# Edin_Usher_DRV2630_reference_design.net
KiCad netlist of a schematic drawn in EAGLE
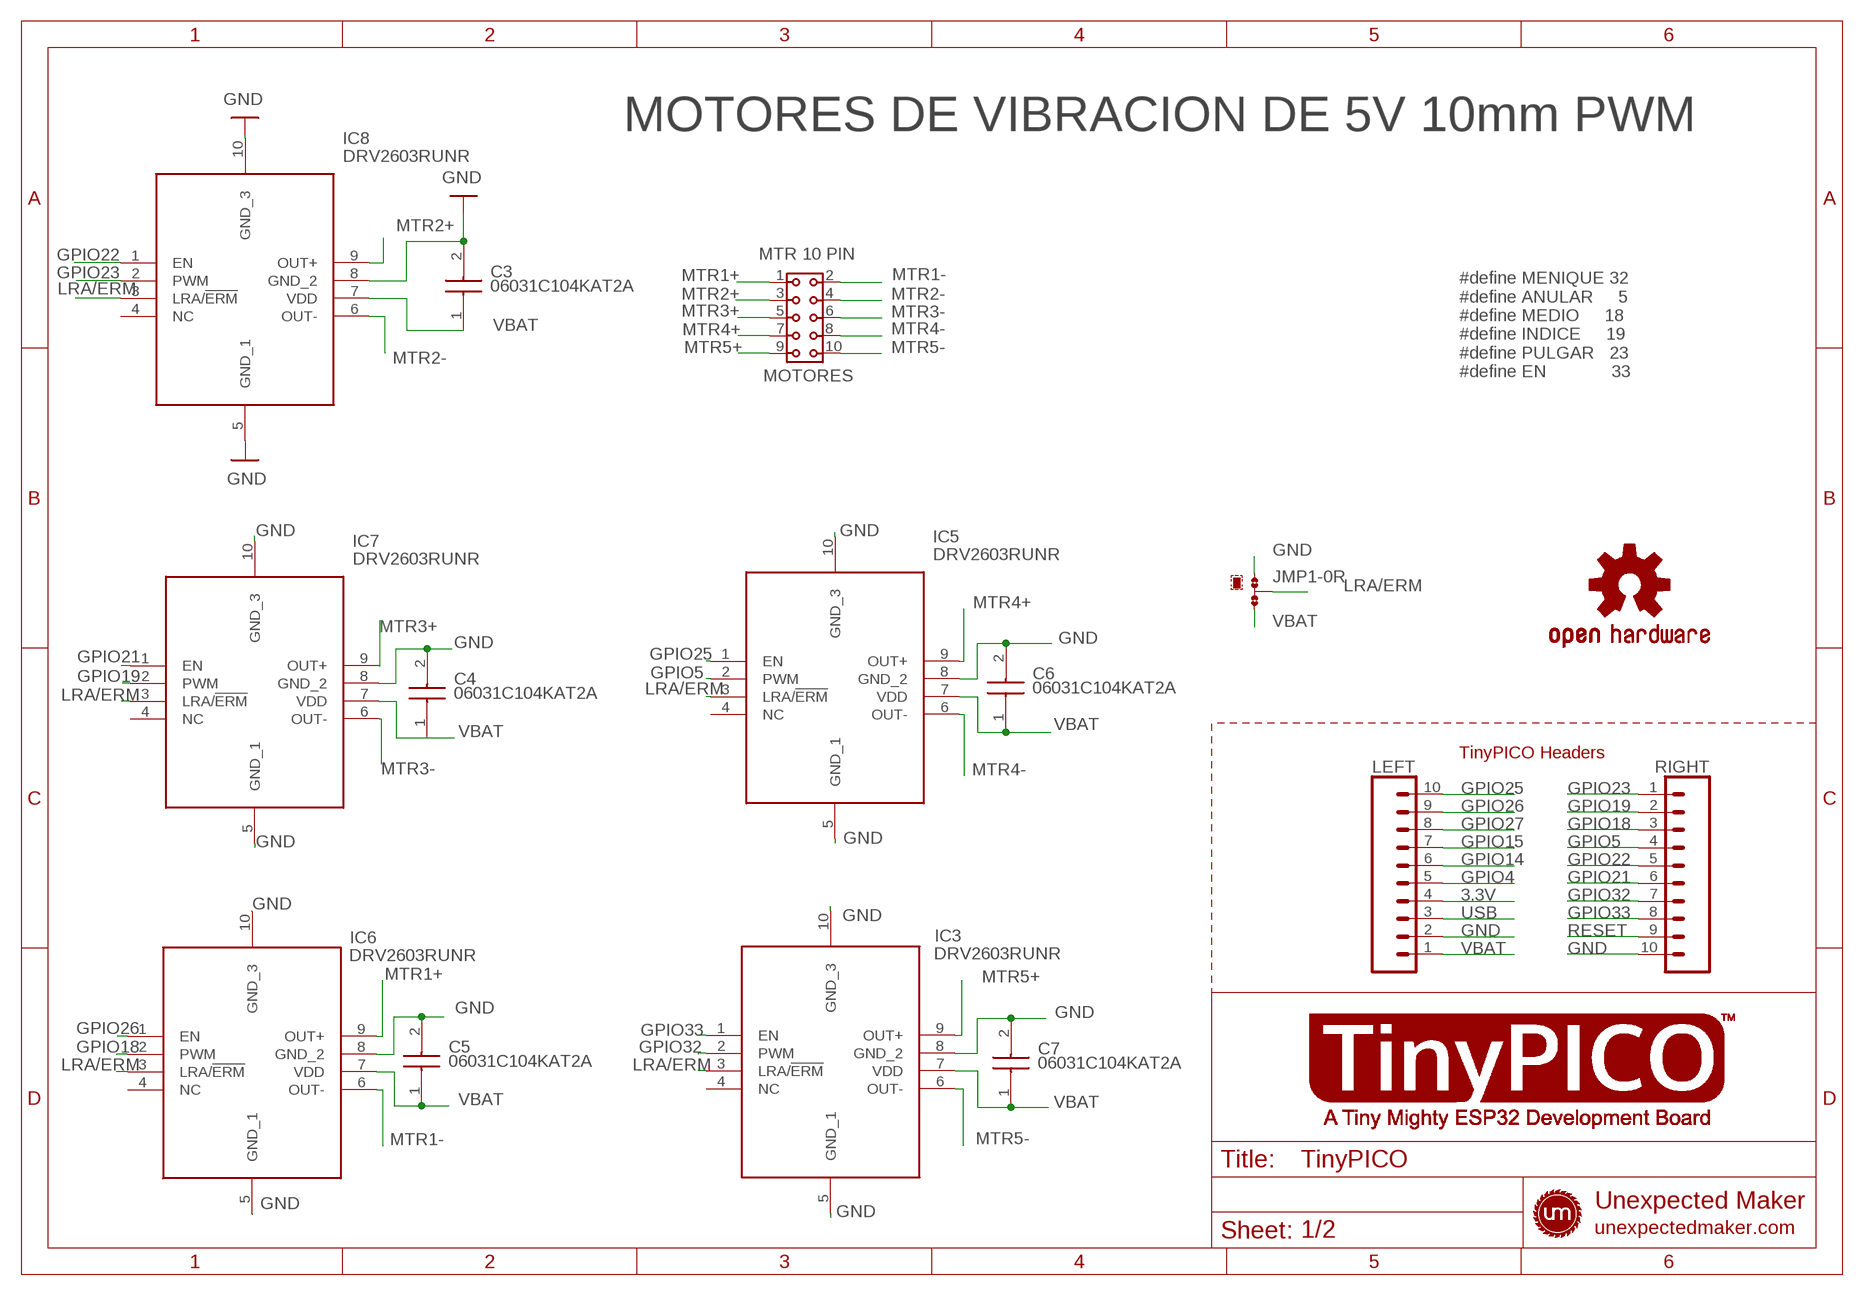
[diagram p0: schematic, sheet 1]
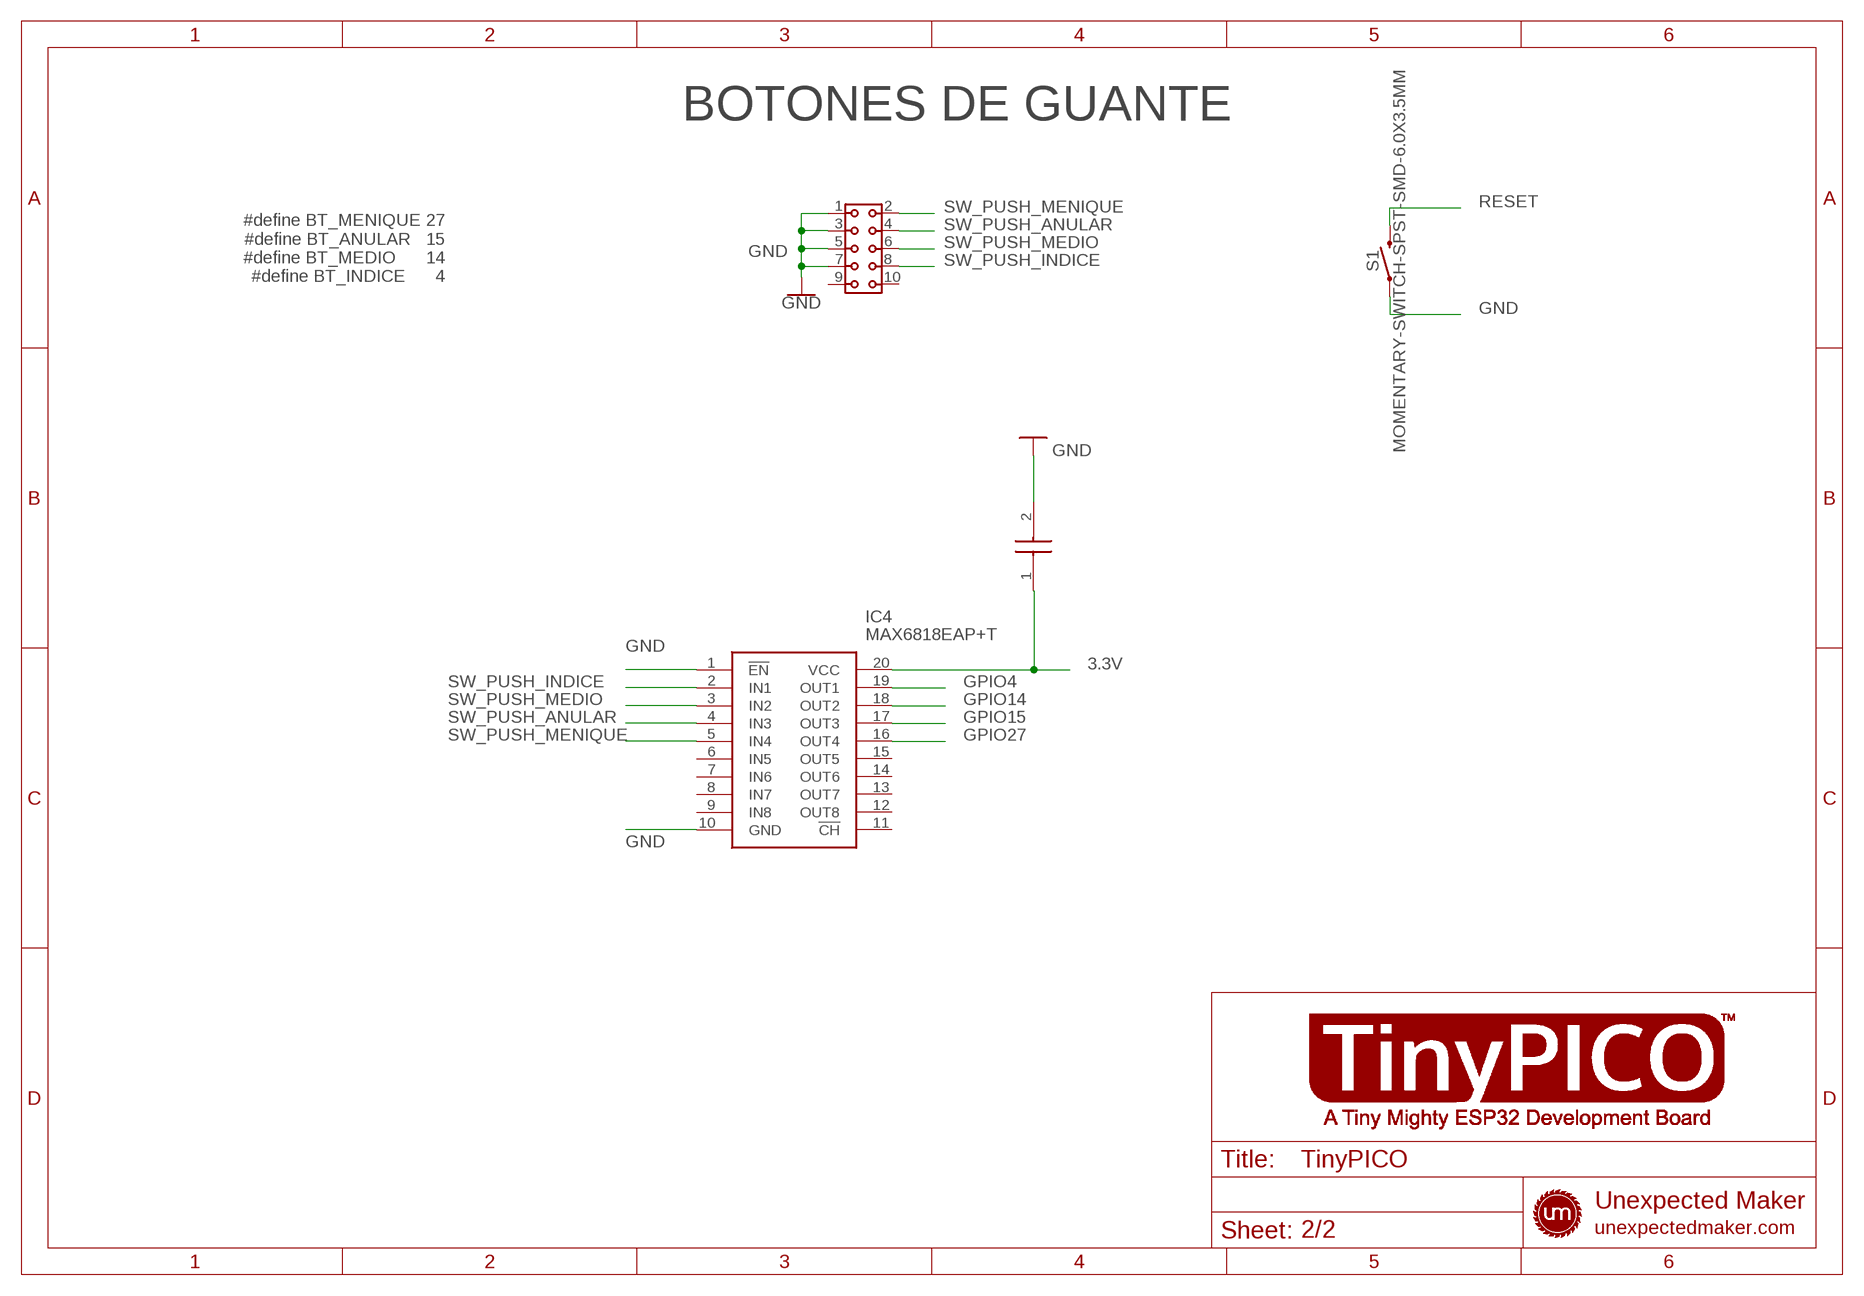
[diagram p1: schematic, sheet 2]

(export (version "E")
  (design (tool "Eeschema 10.0.6"))
  (components
    (comp (ref "C3")
      (value "06031C104KAT2A")
      (footprint "eagle-import:CAPC1608X90N")
      (fields (field (name "MOUSER_PART_NUMBER") "581-06031C104KAT2A"))
      (libsource (lib "eagle-import") (part "06031C104KAT2A"))
    )
    (comp (ref "C4")
      (value "06031C104KAT2A")
      (footprint "eagle-import:CAPC1608X90N")
      (fields (field (name "MOUSER_PART_NUMBER") "581-06031C104KAT2A"))
      (libsource (lib "eagle-import") (part "06031C104KAT2A"))
    )
    (comp (ref "C5")
      (value "06031C104KAT2A")
      (footprint "eagle-import:CAPC1608X90N")
      (fields (field (name "MOUSER_PART_NUMBER") "581-06031C104KAT2A"))
      (libsource (lib "eagle-import") (part "06031C104KAT2A"))
    )
    (comp (ref "C6")
      (value "06031C104KAT2A")
      (footprint "eagle-import:CAPC1608X90N")
      (fields (field (name "MOUSER_PART_NUMBER") "581-06031C104KAT2A"))
      (libsource (lib "eagle-import") (part "06031C104KAT2A"))
    )
    (comp (ref "C7")
      (value "06031C104KAT2A")
      (footprint "eagle-import:CAPC1608X90N")
      (fields (field (name "MOUSER_PART_NUMBER") "581-06031C104KAT2A"))
      (libsource (lib "eagle-import") (part "06031C104KAT2A"))
    )
    (comp (ref "IC3")
      (value "DRV2603RUNR")
      (footprint "eagle-import:QFN50P200X200X80-10N")
      (fields (field (name "MOUSER_PART_NUMBER") "595-DRV2603RUNR"))
      (libsource (lib "eagle-import") (part "DRV2603RUNR"))
    )
    (comp (ref "IC5")
      (value "DRV2603RUNR")
      (footprint "eagle-import:QFN50P200X200X80-10N")
      (fields (field (name "MOUSER_PART_NUMBER") "595-DRV2603RUNR"))
      (libsource (lib "eagle-import") (part "DRV2603RUNR"))
    )
    (comp (ref "IC6")
      (value "DRV2603RUNR")
      (footprint "eagle-import:QFN50P200X200X80-10N")
      (fields (field (name "MOUSER_PART_NUMBER") "595-DRV2603RUNR"))
      (libsource (lib "eagle-import") (part "DRV2603RUNR"))
    )
    (comp (ref "IC7")
      (value "DRV2603RUNR")
      (footprint "eagle-import:QFN50P200X200X80-10N")
      (fields (field (name "MOUSER_PART_NUMBER") "595-DRV2603RUNR"))
      (libsource (lib "eagle-import") (part "DRV2603RUNR"))
    )
    (comp (ref "IC8")
      (value "DRV2603RUNR")
      (footprint "eagle-import:QFN50P200X200X80-10N")
      (fields (field (name "MOUSER_PART_NUMBER") "595-DRV2603RUNR"))
      (libsource (lib "eagle-import") (part "DRV2603RUNR"))
    )
    (comp (ref "JMP1")
      (value "0R-JUMPA")
      (footprint "eagle-import:A0R-JMP")
      (libsource (lib "eagle-import") (part "0R-JUMPA"))
    )
    (comp (ref "LEFT")
      (value "TINYPICO_HEADER_10NO_SILK_PTH_FEMALE")
      (footprint "eagle-import:1X10_NO_SILK")
      (libsource (lib "eagle-import") (part "TINYPICO_HEADER_10NO_SILK_PTH_FEMALE"))
    )
    (comp (ref "LOGO1")
      (value "OSHW-LOGOS")
      (footprint "eagle-import:OSHW-LOGO-S")
      (libsource (lib "eagle-import") (part "OSHW-LOGOS"))
    )
    (comp (ref "MOTORES")
      (value "MTR 10 PIN")
      (footprint "eagle-import:61301021821")
      (libsource (lib "eagle-import") (part "6130XX21821_61301021821"))
    )
    (comp (ref "RIGHT")
      (value "TINYPICO_HEADER_10NO_SILK_PTH_FEMALE")
      (footprint "eagle-import:1X10_NO_SILK")
      (libsource (lib "eagle-import") (part "TINYPICO_HEADER_10NO_SILK_PTH_FEMALE"))
    )
    (comp (ref "BOTONES")
      (value "BTN 10 PIN")
      (footprint "eagle-import:61301021821")
      (libsource (lib "eagle-import") (part "6130XX21821_61301021821"))
    )
    (comp (ref "C8")
      (value "0603B104K160CT")
      (footprint "eagle-import:CAPC1608X87N")
      (fields (field (name "MOUSER_PART_NUMBER") "791-0603B104K160CT"))
      (libsource (lib "eagle-import") (part "0603B104K160CT"))
    )
    (comp (ref "IC4")
      (value "MAX6818EAP+T")
      (footprint "eagle-import:SOP65P778X199-20N")
      (fields (field (name "MOUSER_PART_NUMBER") "700-MAX6818EAPT"))
      (libsource (lib "eagle-import") (part "MAX6818EAP+T"))
    )
    (comp (ref "S1")
      (value "MOMENTARY-SWITCH-SPST-SMD-6.0X3.5MM")
      (footprint "eagle-import:TACTILE_SWITCH_SMD_6.0X3.5MM")
      (libsource (lib "eagle-import") (part "MOMENTARY-SWITCH-SPST-SMD-6.0X3.5MM"))
    )
  )
  (nets
    (net (code "1") (name "3.3V") (class "Default")
      (node (ref "C8") (pin "1") (pinfunction "1_1") (pintype "bidirectional"))
      (node (ref "IC4") (pin "20") (pinfunction "VCC_20") (pintype "power_in"))
      (node (ref "LEFT") (pin "4") (pinfunction "4_4") (pintype "passive"))
    )
    (net (code "2") (name "GND") (class "Default")
      (node (ref "BOTONES") (pin "1") (pinfunction "1_1") (pintype "passive"))
      (node (ref "BOTONES") (pin "3") (pinfunction "3_3") (pintype "passive"))
      (node (ref "BOTONES") (pin "5") (pinfunction "5_5") (pintype "passive"))
      (node (ref "BOTONES") (pin "7") (pinfunction "7_7") (pintype "passive"))
      (node (ref "C3") (pin "2") (pinfunction "2_2") (pintype "bidirectional"))
      (node (ref "C4") (pin "2") (pinfunction "2_2") (pintype "bidirectional"))
      (node (ref "C5") (pin "2") (pinfunction "2_2") (pintype "bidirectional"))
      (node (ref "C6") (pin "2") (pinfunction "2_2") (pintype "bidirectional"))
      (node (ref "C7") (pin "2") (pinfunction "2_2") (pintype "bidirectional"))
      (node (ref "C8") (pin "2") (pinfunction "2_2") (pintype "bidirectional"))
      (node (ref "IC3") (pin "10") (pinfunction "GND_3_10") (pintype "power_in"))
      (node (ref "IC3") (pin "5") (pinfunction "GND_1_5") (pintype "power_in"))
      (node (ref "IC3") (pin "8") (pinfunction "GND_2_8") (pintype "power_in"))
      (node (ref "IC4") (pin "1") (pinfunction "~{EN}_1") (pintype "input"))
      (node (ref "IC4") (pin "10") (pinfunction "GND_10") (pintype "power_in"))
      (node (ref "IC5") (pin "10") (pinfunction "GND_3_10") (pintype "power_in"))
      (node (ref "IC5") (pin "5") (pinfunction "GND_1_5") (pintype "power_in"))
      (node (ref "IC5") (pin "8") (pinfunction "GND_2_8") (pintype "power_in"))
      (node (ref "IC6") (pin "10") (pinfunction "GND_3_10") (pintype "power_in"))
      (node (ref "IC6") (pin "5") (pinfunction "GND_1_5") (pintype "power_in"))
      (node (ref "IC6") (pin "8") (pinfunction "GND_2_8") (pintype "power_in"))
      (node (ref "IC7") (pin "10") (pinfunction "GND_3_10") (pintype "power_in"))
      (node (ref "IC7") (pin "5") (pinfunction "GND_1_5") (pintype "power_in"))
      (node (ref "IC7") (pin "8") (pinfunction "GND_2_8") (pintype "power_in"))
      (node (ref "IC8") (pin "10") (pinfunction "GND_3_10") (pintype "power_in"))
      (node (ref "IC8") (pin "5") (pinfunction "GND_1_5") (pintype "power_in"))
      (node (ref "IC8") (pin "8") (pinfunction "GND_2_8") (pintype "power_in"))
      (node (ref "JMP1") (pin "1") (pinfunction "1_1") (pintype "passive"))
      (node (ref "LEFT") (pin "2") (pinfunction "2_2") (pintype "passive"))
      (node (ref "RIGHT") (pin "10") (pinfunction "10_10") (pintype "passive"))
      (node (ref "S1") (pin "1") (pinfunction "1_1") (pintype "passive"))
    )
    (net (code "3") (name "GPIO4") (class "Default")
      (node (ref "IC4") (pin "19") (pinfunction "OUT1_19") (pintype "output"))
      (node (ref "LEFT") (pin "5") (pinfunction "5_5") (pintype "passive"))
    )
    (net (code "4") (name "GPIO5") (class "Default")
      (node (ref "IC5") (pin "2") (pinfunction "PWM_2") (pintype "input"))
      (node (ref "RIGHT") (pin "4") (pinfunction "4_4") (pintype "passive"))
    )
    (net (code "5") (name "GPIO14") (class "Default")
      (node (ref "IC4") (pin "18") (pinfunction "OUT2_18") (pintype "output"))
      (node (ref "LEFT") (pin "6") (pinfunction "6_6") (pintype "passive"))
    )
    (net (code "6") (name "GPIO15") (class "Default")
      (node (ref "IC4") (pin "17") (pinfunction "OUT3_17") (pintype "output"))
      (node (ref "LEFT") (pin "7") (pinfunction "7_7") (pintype "passive"))
    )
    (net (code "7") (name "GPIO18") (class "Default")
      (node (ref "IC6") (pin "2") (pinfunction "PWM_2") (pintype "input"))
      (node (ref "RIGHT") (pin "3") (pinfunction "3_3") (pintype "passive"))
    )
    (net (code "8") (name "GPIO19") (class "Default")
      (node (ref "IC7") (pin "2") (pinfunction "PWM_2") (pintype "input"))
      (node (ref "RIGHT") (pin "2") (pinfunction "2_2") (pintype "passive"))
    )
    (net (code "9") (name "GPIO21") (class "Default")
      (node (ref "IC7") (pin "1") (pinfunction "EN_1") (pintype "input"))
      (node (ref "RIGHT") (pin "6") (pinfunction "6_6") (pintype "passive"))
    )
    (net (code "10") (name "GPIO22") (class "Default")
      (node (ref "IC8") (pin "1") (pinfunction "EN_1") (pintype "input"))
      (node (ref "RIGHT") (pin "5") (pinfunction "5_5") (pintype "passive"))
    )
    (net (code "11") (name "GPIO23") (class "Default")
      (node (ref "IC8") (pin "2") (pinfunction "PWM_2") (pintype "input"))
      (node (ref "RIGHT") (pin "1") (pinfunction "1_1") (pintype "passive"))
    )
    (net (code "12") (name "GPIO25") (class "Default")
      (node (ref "IC5") (pin "1") (pinfunction "EN_1") (pintype "input"))
      (node (ref "LEFT") (pin "10") (pinfunction "10_10") (pintype "passive"))
    )
    (net (code "13") (name "GPIO26") (class "Default")
      (node (ref "IC6") (pin "1") (pinfunction "EN_1") (pintype "input"))
      (node (ref "LEFT") (pin "9") (pinfunction "9_9") (pintype "passive"))
    )
    (net (code "14") (name "GPIO27") (class "Default")
      (node (ref "IC4") (pin "16") (pinfunction "OUT4_16") (pintype "output"))
      (node (ref "LEFT") (pin "8") (pinfunction "8_8") (pintype "passive"))
    )
    (net (code "15") (name "GPIO32") (class "Default")
      (node (ref "IC3") (pin "2") (pinfunction "PWM_2") (pintype "input"))
      (node (ref "RIGHT") (pin "7") (pinfunction "7_7") (pintype "passive"))
    )
    (net (code "16") (name "GPIO33") (class "Default")
      (node (ref "IC3") (pin "1") (pinfunction "EN_1") (pintype "input"))
      (node (ref "RIGHT") (pin "8") (pinfunction "8_8") (pintype "passive"))
    )
    (net (code "17") (name "LRA{slash}ERM") (class "Default")
      (node (ref "IC3") (pin "3") (pinfunction "LRA/~{ERM}_3") (pintype "input"))
      (node (ref "IC5") (pin "3") (pinfunction "LRA/~{ERM}_3") (pintype "input"))
      (node (ref "IC6") (pin "3") (pinfunction "LRA/~{ERM}_3") (pintype "input"))
      (node (ref "IC7") (pin "3") (pinfunction "LRA/~{ERM}_3") (pintype "input"))
      (node (ref "IC8") (pin "3") (pinfunction "LRA/~{ERM}_3") (pintype "input"))
      (node (ref "JMP1") (pin "2") (pinfunction "2_2") (pintype "passive"))
    )
    (net (code "18") (name "MTR1+") (class "Default")
      (node (ref "IC6") (pin "9") (pinfunction "OUT+_9") (pintype "output"))
      (node (ref "MOTORES") (pin "1") (pinfunction "1_1") (pintype "passive"))
    )
    (net (code "19") (name "MTR1-") (class "Default")
      (node (ref "IC6") (pin "6") (pinfunction "OUT-_6") (pintype "output"))
      (node (ref "MOTORES") (pin "2") (pinfunction "2_2") (pintype "passive"))
    )
    (net (code "20") (name "MTR2+") (class "Default")
      (node (ref "IC8") (pin "9") (pinfunction "OUT+_9") (pintype "output"))
      (node (ref "MOTORES") (pin "3") (pinfunction "3_3") (pintype "passive"))
    )
    (net (code "21") (name "MTR2-") (class "Default")
      (node (ref "IC8") (pin "6") (pinfunction "OUT-_6") (pintype "output"))
      (node (ref "MOTORES") (pin "4") (pinfunction "4_4") (pintype "passive"))
    )
    (net (code "22") (name "MTR3+") (class "Default")
      (node (ref "IC7") (pin "9") (pinfunction "OUT+_9") (pintype "output"))
      (node (ref "MOTORES") (pin "5") (pinfunction "5_5") (pintype "passive"))
    )
    (net (code "23") (name "MTR3-") (class "Default")
      (node (ref "IC7") (pin "6") (pinfunction "OUT-_6") (pintype "output"))
      (node (ref "MOTORES") (pin "6") (pinfunction "6_6") (pintype "passive"))
    )
    (net (code "24") (name "MTR4+") (class "Default")
      (node (ref "IC5") (pin "9") (pinfunction "OUT+_9") (pintype "output"))
      (node (ref "MOTORES") (pin "7") (pinfunction "7_7") (pintype "passive"))
    )
    (net (code "25") (name "MTR4-") (class "Default")
      (node (ref "IC5") (pin "6") (pinfunction "OUT-_6") (pintype "output"))
      (node (ref "MOTORES") (pin "8") (pinfunction "8_8") (pintype "passive"))
    )
    (net (code "26") (name "MTR5+") (class "Default")
      (node (ref "IC3") (pin "9") (pinfunction "OUT+_9") (pintype "output"))
      (node (ref "MOTORES") (pin "9") (pinfunction "9_9") (pintype "passive"))
    )
    (net (code "27") (name "MTR5-") (class "Default")
      (node (ref "IC3") (pin "6") (pinfunction "OUT-_6") (pintype "output"))
      (node (ref "MOTORES") (pin "10") (pinfunction "10_10") (pintype "passive"))
    )
    (net (code "28") (name "RESET") (class "Default")
      (node (ref "RIGHT") (pin "9") (pinfunction "9_9") (pintype "passive"))
      (node (ref "S1") (pin "2") (pinfunction "2_2") (pintype "passive"))
    )
    (net (code "29") (name "SW_PUSH_ANULAR") (class "Default")
      (node (ref "BOTONES") (pin "4") (pinfunction "4_4") (pintype "passive"))
      (node (ref "IC4") (pin "4") (pinfunction "IN3_4") (pintype "input"))
    )
    (net (code "30") (name "SW_PUSH_INDICE") (class "Default")
      (node (ref "BOTONES") (pin "8") (pinfunction "8_8") (pintype "passive"))
      (node (ref "IC4") (pin "2") (pinfunction "IN1_2") (pintype "input"))
    )
    (net (code "31") (name "SW_PUSH_MEDIO") (class "Default")
      (node (ref "BOTONES") (pin "6") (pinfunction "6_6") (pintype "passive"))
      (node (ref "IC4") (pin "3") (pinfunction "IN2_3") (pintype "input"))
    )
    (net (code "32") (name "SW_PUSH_MENIQUE") (class "Default")
      (node (ref "BOTONES") (pin "2") (pinfunction "2_2") (pintype "passive"))
      (node (ref "IC4") (pin "5") (pinfunction "IN4_5") (pintype "input"))
    )
    (net (code "33") (name "USB") (class "Default")
      (node (ref "LEFT") (pin "3") (pinfunction "3_3") (pintype "passive"))
    )
    (net (code "34") (name "VBAT") (class "Default")
      (node (ref "C3") (pin "1") (pinfunction "1_1") (pintype "bidirectional"))
      (node (ref "C4") (pin "1") (pinfunction "1_1") (pintype "bidirectional"))
      (node (ref "C5") (pin "1") (pinfunction "1_1") (pintype "bidirectional"))
      (node (ref "C6") (pin "1") (pinfunction "1_1") (pintype "bidirectional"))
      (node (ref "C7") (pin "1") (pinfunction "1_1") (pintype "bidirectional"))
      (node (ref "IC3") (pin "7") (pinfunction "VDD_7") (pintype "power_in"))
      (node (ref "IC5") (pin "7") (pinfunction "VDD_7") (pintype "power_in"))
      (node (ref "IC6") (pin "7") (pinfunction "VDD_7") (pintype "power_in"))
      (node (ref "IC7") (pin "7") (pinfunction "VDD_7") (pintype "power_in"))
      (node (ref "IC8") (pin "7") (pinfunction "VDD_7") (pintype "power_in"))
      (node (ref "JMP1") (pin "3") (pinfunction "3_3") (pintype "passive"))
      (node (ref "LEFT") (pin "1") (pinfunction "1_1") (pintype "passive"))
    )
    (net (code "35") (name "unconnected-(BOTONES-Pad9)") (class "Default")
      (node (ref "BOTONES") (pin "9") (pinfunction "9_9") (pintype "passive"))
    )
    (net (code "36") (name "unconnected-(BOTONES-Pad10)") (class "Default")
      (node (ref "BOTONES") (pin "10") (pinfunction "10_10") (pintype "passive"))
    )
    (net (code "37") (name "unconnected-(IC3-NC-Pad4)") (class "Default")
      (node (ref "IC3") (pin "4") (pinfunction "NC_4") (pintype "no_connect"))
    )
    (net (code "38") (name "unconnected-(IC4-IN5-Pad6)") (class "Default")
      (node (ref "IC4") (pin "6") (pinfunction "IN5_6") (pintype "input"))
    )
    (net (code "39") (name "unconnected-(IC4-IN6-Pad7)") (class "Default")
      (node (ref "IC4") (pin "7") (pinfunction "IN6_7") (pintype "input"))
    )
    (net (code "40") (name "unconnected-(IC4-IN7-Pad8)") (class "Default")
      (node (ref "IC4") (pin "8") (pinfunction "IN7_8") (pintype "input"))
    )
    (net (code "41") (name "unconnected-(IC4-IN8-Pad9)") (class "Default")
      (node (ref "IC4") (pin "9") (pinfunction "IN8_9") (pintype "input"))
    )
    (net (code "42") (name "unconnected-(IC4-OUT5-Pad15)") (class "Default")
      (node (ref "IC4") (pin "15") (pinfunction "OUT5_15") (pintype "output"))
    )
    (net (code "43") (name "unconnected-(IC4-OUT6-Pad14)") (class "Default")
      (node (ref "IC4") (pin "14") (pinfunction "OUT6_14") (pintype "output"))
    )
    (net (code "44") (name "unconnected-(IC4-OUT7-Pad13)") (class "Default")
      (node (ref "IC4") (pin "13") (pinfunction "OUT7_13") (pintype "output"))
    )
    (net (code "45") (name "unconnected-(IC4-OUT8-Pad12)") (class "Default")
      (node (ref "IC4") (pin "12") (pinfunction "OUT8_12") (pintype "output"))
    )
    (net (code "46") (name "unconnected-(IC4-~{CH}-Pad11)") (class "Default")
      (node (ref "IC4") (pin "11") (pinfunction "~{CH}_11") (pintype "output"))
    )
    (net (code "47") (name "unconnected-(IC5-NC-Pad4)") (class "Default")
      (node (ref "IC5") (pin "4") (pinfunction "NC_4") (pintype "no_connect"))
    )
    (net (code "48") (name "unconnected-(IC6-NC-Pad4)") (class "Default")
      (node (ref "IC6") (pin "4") (pinfunction "NC_4") (pintype "no_connect"))
    )
    (net (code "49") (name "unconnected-(IC7-NC-Pad4)") (class "Default")
      (node (ref "IC7") (pin "4") (pinfunction "NC_4") (pintype "no_connect"))
    )
    (net (code "50") (name "unconnected-(IC8-NC-Pad4)") (class "Default")
      (node (ref "IC8") (pin "4") (pinfunction "NC_4") (pintype "no_connect"))
    )
  )
)
